# LawnBot.net
KiCad netlist of a schematic drawn in EasyEDA
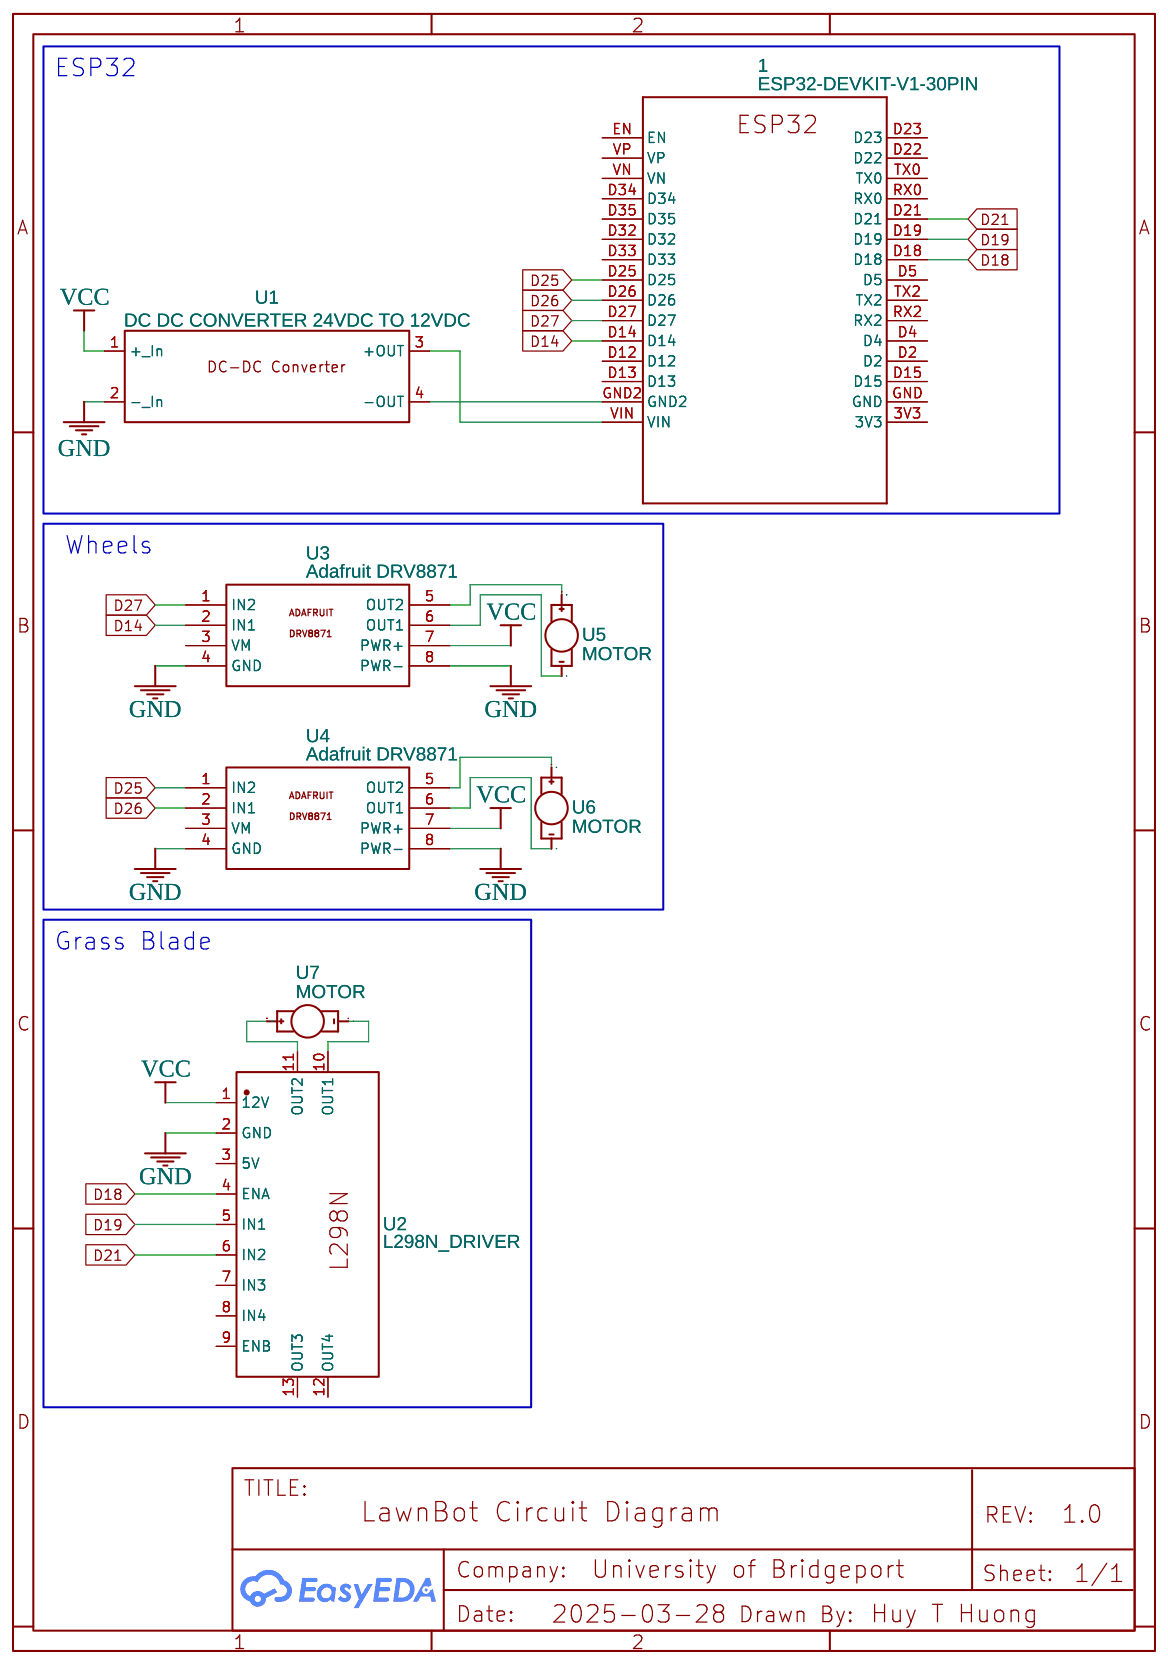
[diagram p0: schematic sheet]

(export (version "E")
  (design (tool "Eeschema 10.0.6"))
  (components
    (comp (ref "1") (value "ESP32-DEVKIT-V1-30PIN") (libsource (lib "") (part "ESP32-DEVKIT-V1-30PIN")))
    (comp (ref "U1")
      (value "DC DC CONVERTER 24VDC TO 12VDC")
      (fields (field (name "Manufacturer Part") "A"))
      (libsource (lib "") (part "DC DC CONVERTER 24VDC TO 12VDC"))
    )
    (comp (ref "U2") (value "L298N_DRIVER") (libsource (lib "") (part "L298N_DRIVER")))
    (comp (ref "U3")
      (value "Adafruit DRV8871")
      (fields (field (name "Manufacturer Part") "3190") (field (name "Manufacturer") "Adafruit"))
      (libsource (lib "") (part "Adafruit DRV8871"))
    )
    (comp (ref "U4")
      (value "Adafruit DRV8871")
      (fields (field (name "Manufacturer Part") "3190") (field (name "Manufacturer") "Adafruit"))
      (libsource (lib "") (part "Adafruit DRV8871"))
    )
    (comp (ref "U5") (value "MOTOR") (libsource (lib "") (part "MOTOR")))
    (comp (ref "U6") (value "MOTOR") (libsource (lib "") (part "MOTOR")))
    (comp (ref "U7") (value "MOTOR") (libsource (lib "") (part "MOTOR_1")))
  )
  (nets
    (net (code "1") (name "D14") (class "Default")
      (node (ref "1") (pin "D14") (pinfunction "D14_D14") (pintype "unspecified"))
      (node (ref "U3") (pin "2") (pinfunction "IN1_2") (pintype "unspecified"))
    )
    (net (code "2") (name "D18") (class "Default")
      (node (ref "1") (pin "D18") (pinfunction "D18_D18") (pintype "unspecified"))
      (node (ref "U2") (pin "4") (pinfunction "ENA_4") (pintype "unspecified"))
    )
    (net (code "3") (name "D19") (class "Default")
      (node (ref "1") (pin "D19") (pinfunction "D19_D19") (pintype "unspecified"))
      (node (ref "U2") (pin "5") (pinfunction "IN1_5") (pintype "unspecified"))
    )
    (net (code "4") (name "D21") (class "Default")
      (node (ref "1") (pin "D21") (pinfunction "D21_D21") (pintype "unspecified"))
      (node (ref "U2") (pin "6") (pinfunction "IN2_6") (pintype "unspecified"))
    )
    (net (code "5") (name "D25") (class "Default")
      (node (ref "1") (pin "D25") (pinfunction "D25_D25") (pintype "unspecified"))
      (node (ref "U4") (pin "1") (pinfunction "IN2_1") (pintype "unspecified"))
    )
    (net (code "6") (name "D26") (class "Default")
      (node (ref "1") (pin "D26") (pinfunction "D26_D26") (pintype "unspecified"))
      (node (ref "U4") (pin "2") (pinfunction "IN1_2") (pintype "unspecified"))
    )
    (net (code "7") (name "D27") (class "Default")
      (node (ref "1") (pin "D27") (pinfunction "D27_D27") (pintype "unspecified"))
      (node (ref "U3") (pin "1") (pinfunction "IN2_1") (pintype "unspecified"))
    )
    (net (code "8") (name "GND") (class "Default")
      (node (ref "U1") (pin "2") (pinfunction "-_In_2") (pintype "unspecified"))
      (node (ref "U2") (pin "2") (pinfunction "GND_2") (pintype "unspecified"))
      (node (ref "U3") (pin "4") (pinfunction "GND_4") (pintype "unspecified"))
      (node (ref "U3") (pin "8") (pinfunction "PWR-_8") (pintype "unspecified"))
      (node (ref "U4") (pin "4") (pinfunction "GND_4") (pintype "unspecified"))
      (node (ref "U4") (pin "8") (pinfunction "PWR-_8") (pintype "unspecified"))
    )
    (net (code "9") (name "Net-(U1-+OUT)") (class "Default")
      (node (ref "1") (pin "VIN") (pinfunction "VIN_VIN") (pintype "unspecified"))
      (node (ref "U1") (pin "3") (pinfunction "+OUT_3") (pintype "unspecified"))
    )
    (net (code "10") (name "Net-(U1--OUT)") (class "Default")
      (node (ref "1") (pin "GND2") (pinfunction "GND2_GND2") (pintype "unspecified"))
      (node (ref "U1") (pin "4") (pinfunction "-OUT_4") (pintype "unspecified"))
    )
    (net (code "11") (name "Net-(U2-OUT1)") (class "Default")
      (node (ref "U2") (pin "10") (pinfunction "OUT1_10") (pintype "unspecified"))
      (node (ref "U7") (pin "-") (pinfunction "-_-") (pintype "unspecified"))
    )
    (net (code "12") (name "Net-(U2-OUT2)") (class "Default")
      (node (ref "U2") (pin "11") (pinfunction "OUT2_11") (pintype "unspecified"))
      (node (ref "U7") (pin "+") (pinfunction "+_+") (pintype "unspecified"))
    )
    (net (code "13") (name "Net-(U3-OUT1)") (class "Default")
      (node (ref "U3") (pin "6") (pinfunction "OUT1_6") (pintype "unspecified"))
      (node (ref "U5") (pin "-") (pinfunction "-_-") (pintype "unspecified"))
    )
    (net (code "14") (name "Net-(U3-OUT2)") (class "Default")
      (node (ref "U3") (pin "5") (pinfunction "OUT2_5") (pintype "unspecified"))
      (node (ref "U5") (pin "+") (pinfunction "+_+") (pintype "unspecified"))
    )
    (net (code "15") (name "Net-(U4-OUT1)") (class "Default")
      (node (ref "U4") (pin "6") (pinfunction "OUT1_6") (pintype "unspecified"))
      (node (ref "U6") (pin "-") (pinfunction "-_-") (pintype "unspecified"))
    )
    (net (code "16") (name "Net-(U4-OUT2)") (class "Default")
      (node (ref "U4") (pin "5") (pinfunction "OUT2_5") (pintype "unspecified"))
      (node (ref "U6") (pin "+") (pinfunction "+_+") (pintype "unspecified"))
    )
    (net (code "17") (name "VCC") (class "Default")
      (node (ref "U1") (pin "1") (pinfunction "+_In_1") (pintype "unspecified"))
      (node (ref "U2") (pin "1") (pinfunction "12V_1") (pintype "unspecified"))
      (node (ref "U3") (pin "7") (pinfunction "PWR+_7") (pintype "unspecified"))
      (node (ref "U4") (pin "7") (pinfunction "PWR+_7") (pintype "unspecified"))
    )
    (net (code "18") (name "unconnected-(1-Pad3V3)") (class "Default")
      (node (ref "1") (pin "3V3") (pinfunction "3V3_3V3") (pintype "unspecified"))
    )
    (net (code "19") (name "unconnected-(1-PadD2)") (class "Default")
      (node (ref "1") (pin "D2") (pinfunction "D2_D2") (pintype "unspecified"))
    )
    (net (code "20") (name "unconnected-(1-PadD4)") (class "Default")
      (node (ref "1") (pin "D4") (pinfunction "D4_D4") (pintype "unspecified"))
    )
    (net (code "21") (name "unconnected-(1-PadD5)") (class "Default")
      (node (ref "1") (pin "D5") (pinfunction "D5_D5") (pintype "unspecified"))
    )
    (net (code "22") (name "unconnected-(1-PadD12)") (class "Default")
      (node (ref "1") (pin "D12") (pinfunction "D12_D12") (pintype "unspecified"))
    )
    (net (code "23") (name "unconnected-(1-PadD13)") (class "Default")
      (node (ref "1") (pin "D13") (pinfunction "D13_D13") (pintype "unspecified"))
    )
    (net (code "24") (name "unconnected-(1-PadD15)") (class "Default")
      (node (ref "1") (pin "D15") (pinfunction "D15_D15") (pintype "unspecified"))
    )
    (net (code "25") (name "unconnected-(1-PadD22)") (class "Default")
      (node (ref "1") (pin "D22") (pinfunction "D22_D22") (pintype "unspecified"))
    )
    (net (code "26") (name "unconnected-(1-PadD23)") (class "Default")
      (node (ref "1") (pin "D23") (pinfunction "D23_D23") (pintype "unspecified"))
    )
    (net (code "27") (name "unconnected-(1-PadD32)") (class "Default")
      (node (ref "1") (pin "D32") (pinfunction "D32_D32") (pintype "unspecified"))
    )
    (net (code "28") (name "unconnected-(1-PadD33)") (class "Default")
      (node (ref "1") (pin "D33") (pinfunction "D33_D33") (pintype "unspecified"))
    )
    (net (code "29") (name "unconnected-(1-PadD34)") (class "Default")
      (node (ref "1") (pin "D34") (pinfunction "D34_D34") (pintype "unspecified"))
    )
    (net (code "30") (name "unconnected-(1-PadD35)") (class "Default")
      (node (ref "1") (pin "D35") (pinfunction "D35_D35") (pintype "unspecified"))
    )
    (net (code "31") (name "unconnected-(1-PadEN)") (class "Default")
      (node (ref "1") (pin "EN") (pinfunction "EN_EN") (pintype "unspecified"))
    )
    (net (code "32") (name "unconnected-(1-PadGND)") (class "Default")
      (node (ref "1") (pin "GND") (pinfunction "GND_GND") (pintype "unspecified"))
    )
    (net (code "33") (name "unconnected-(1-PadRX0)") (class "Default")
      (node (ref "1") (pin "RX0") (pinfunction "RX0_RX0") (pintype "unspecified"))
    )
    (net (code "34") (name "unconnected-(1-PadRX2)") (class "Default")
      (node (ref "1") (pin "RX2") (pinfunction "RX2_RX2") (pintype "unspecified"))
    )
    (net (code "35") (name "unconnected-(1-PadTX0)") (class "Default")
      (node (ref "1") (pin "TX0") (pinfunction "TX0_TX0") (pintype "unspecified"))
    )
    (net (code "36") (name "unconnected-(1-PadTX2)") (class "Default")
      (node (ref "1") (pin "TX2") (pinfunction "TX2_TX2") (pintype "unspecified"))
    )
    (net (code "37") (name "unconnected-(1-PadVN)") (class "Default")
      (node (ref "1") (pin "VN") (pinfunction "VN_VN") (pintype "unspecified"))
    )
    (net (code "38") (name "unconnected-(1-PadVP)") (class "Default")
      (node (ref "1") (pin "VP") (pinfunction "VP_VP") (pintype "unspecified"))
    )
    (net (code "39") (name "unconnected-(U2-5V-Pad3)") (class "Default")
      (node (ref "U2") (pin "3") (pinfunction "5V_3") (pintype "unspecified"))
    )
    (net (code "40") (name "unconnected-(U2-ENB-Pad9)") (class "Default")
      (node (ref "U2") (pin "9") (pinfunction "ENB_9") (pintype "unspecified"))
    )
    (net (code "41") (name "unconnected-(U2-IN3-Pad7)") (class "Default")
      (node (ref "U2") (pin "7") (pinfunction "IN3_7") (pintype "unspecified"))
    )
    (net (code "42") (name "unconnected-(U2-IN4-Pad8)") (class "Default")
      (node (ref "U2") (pin "8") (pinfunction "IN4_8") (pintype "unspecified"))
    )
    (net (code "43") (name "unconnected-(U2-OUT3-Pad13)") (class "Default")
      (node (ref "U2") (pin "13") (pinfunction "OUT3_13") (pintype "unspecified"))
    )
    (net (code "44") (name "unconnected-(U2-OUT4-Pad12)") (class "Default")
      (node (ref "U2") (pin "12") (pinfunction "OUT4_12") (pintype "unspecified"))
    )
    (net (code "45") (name "unconnected-(U3-VM-Pad3)") (class "Default")
      (node (ref "U3") (pin "3") (pinfunction "VM_3") (pintype "unspecified"))
    )
    (net (code "46") (name "unconnected-(U4-VM-Pad3)") (class "Default")
      (node (ref "U4") (pin "3") (pinfunction "VM_3") (pintype "unspecified"))
    )
  )
)
